# POVwatch_1.net
KiCad netlist of a schematic drawn in EAGLE
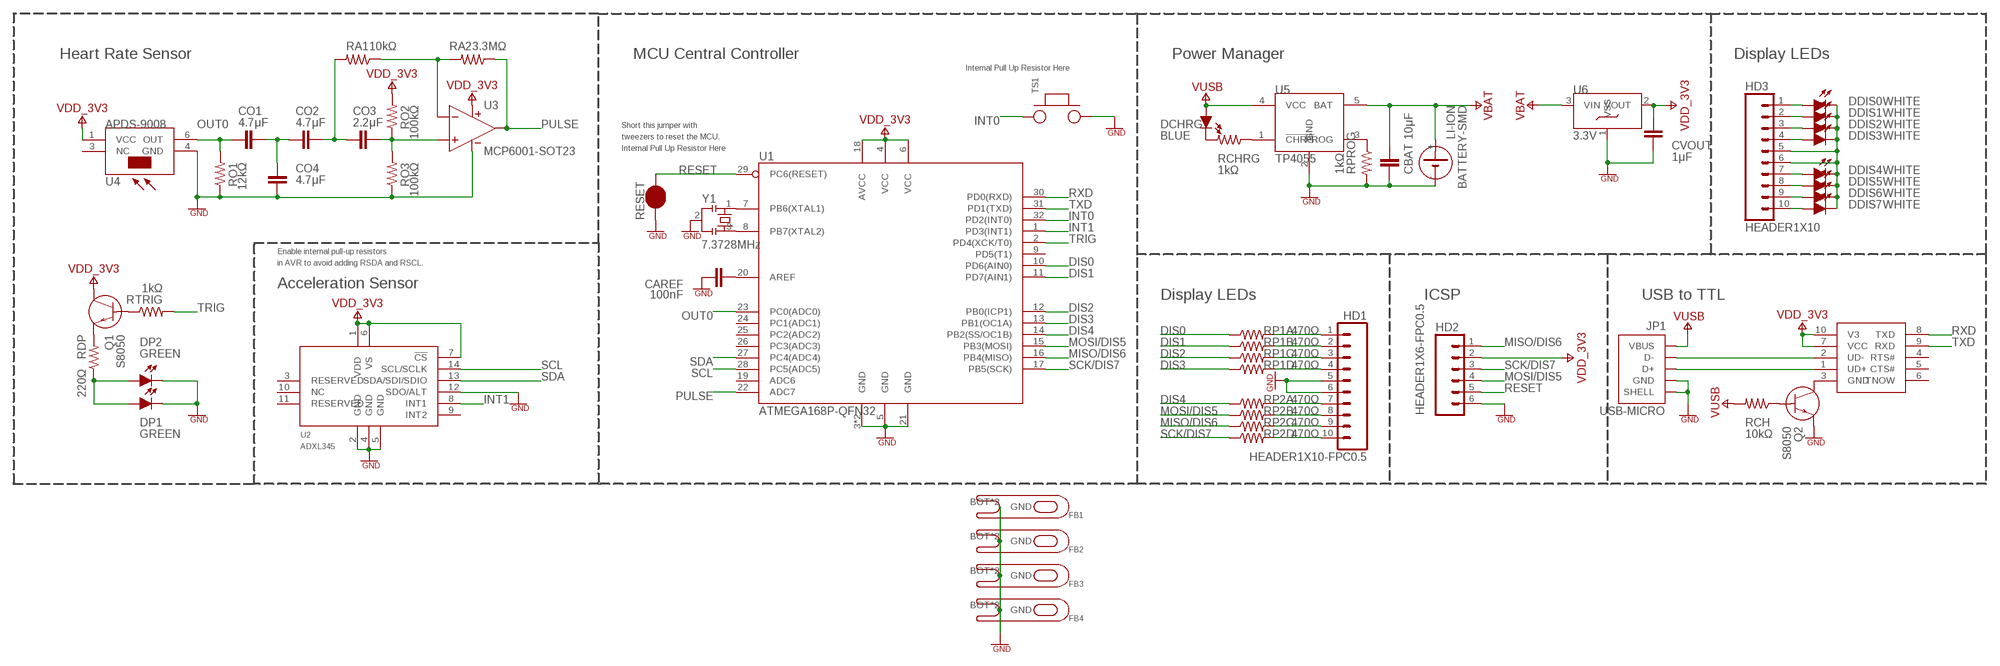
[diagram p0: schematic, sheet 1]

(export (version "E")
  (design (tool "Eeschema 10.0.6"))
  (components
    (comp (ref "CAREF")
      (value "100nF")
      (footprint "eagle-import:SMD0603")
      (libsource (lib "eagle-import") (part "CAP-0603"))
    )
    (comp (ref "CBAT")
      (value "10μF")
      (footprint "eagle-import:SMD0603")
      (libsource (lib "eagle-import") (part "CAP-0603"))
    )
    (comp (ref "CO1")
      (value "4.7μF")
      (footprint "eagle-import:SMD0603")
      (libsource (lib "eagle-import") (part "CAP-0603"))
    )
    (comp (ref "CO2")
      (value "4.7μF")
      (footprint "eagle-import:SMD0603")
      (libsource (lib "eagle-import") (part "CAP-0603"))
    )
    (comp (ref "CO3")
      (value "2.2μF")
      (footprint "eagle-import:SMD0603")
      (libsource (lib "eagle-import") (part "CAP-0603"))
    )
    (comp (ref "CO4")
      (value "4.7μF")
      (footprint "eagle-import:SMD0603")
      (libsource (lib "eagle-import") (part "CAP-0603"))
    )
    (comp (ref "CVOUT")
      (value "1μF")
      (footprint "eagle-import:SMD0603")
      (libsource (lib "eagle-import") (part "CAP-0603"))
    )
    (comp (ref "DCHRG")
      (value "BLUE")
      (footprint "eagle-import:LED-0603")
      (libsource (lib "eagle-import") (part "LED-0603"))
    )
    (comp (ref "DDIS0")
      (value "WHITE")
      (footprint "eagle-import:LED-0603")
      (libsource (lib "eagle-import") (part "LED-0603"))
    )
    (comp (ref "DDIS1")
      (value "WHITE")
      (footprint "eagle-import:LED-0603")
      (libsource (lib "eagle-import") (part "LED-0603"))
    )
    (comp (ref "DDIS2")
      (value "WHITE")
      (footprint "eagle-import:LED-0603")
      (libsource (lib "eagle-import") (part "LED-0603"))
    )
    (comp (ref "DDIS3")
      (value "WHITE")
      (footprint "eagle-import:LED-0603")
      (libsource (lib "eagle-import") (part "LED-0603"))
    )
    (comp (ref "DDIS4")
      (value "WHITE")
      (footprint "eagle-import:LED-0603")
      (libsource (lib "eagle-import") (part "LED-0603"))
    )
    (comp (ref "DDIS5")
      (value "WHITE")
      (footprint "eagle-import:LED-0603")
      (libsource (lib "eagle-import") (part "LED-0603"))
    )
    (comp (ref "DDIS6")
      (value "WHITE")
      (footprint "eagle-import:LED-0603")
      (libsource (lib "eagle-import") (part "LED-0603"))
    )
    (comp (ref "DDIS7")
      (value "WHITE")
      (footprint "eagle-import:LED-0603")
      (libsource (lib "eagle-import") (part "LED-0603"))
    )
    (comp (ref "DP1")
      (value "GREEN")
      (footprint "eagle-import:LED-1206")
      (libsource (lib "eagle-import") (part "LED-1206"))
    )
    (comp (ref "DP2")
      (value "GREEN")
      (footprint "eagle-import:LED-1206")
      (libsource (lib "eagle-import") (part "LED-1206"))
    )
    (comp (ref "FB1")
      (value "BROAD-STICK")
      (footprint "eagle-import:BOARD-STICK")
      (libsource (lib "eagle-import") (part "BROAD-STICK"))
    )
    (comp (ref "FB2")
      (value "BROAD-STICK")
      (footprint "eagle-import:BOARD-STICK")
      (libsource (lib "eagle-import") (part "BROAD-STICK"))
    )
    (comp (ref "FB3")
      (value "BROAD-STICK")
      (footprint "eagle-import:BOARD-STICK")
      (libsource (lib "eagle-import") (part "BROAD-STICK"))
    )
    (comp (ref "FB4")
      (value "BROAD-STICK")
      (footprint "eagle-import:BOARD-STICK")
      (libsource (lib "eagle-import") (part "BROAD-STICK"))
    )
    (comp (ref "HD1")
      (value "HEADER1X10-FPC0.5")
      (footprint "eagle-import:FPC0.5-10")
      (libsource (lib "eagle-import") (part "HEADER1X10-FPC0.5"))
    )
    (comp (ref "HD2")
      (value "HEADER1X6-FPC0.5")
      (footprint "eagle-import:FPC0.5-6")
      (libsource (lib "eagle-import") (part "HEADER1X6-FPC0.5"))
    )
    (comp (ref "HD3")
      (value "HEADER1X10")
      (footprint "eagle-import:FPC0.5-10-SOLDER")
      (libsource (lib "eagle-import") (part "HEADER1X10"))
    )
    (comp (ref "JP1")
      (value "USB-MICRO")
      (footprint "eagle-import:USB-MICRO")
      (libsource (lib "eagle-import") (part "USB-MICRO"))
    )
    (comp (ref "LI-ION")
      (value "BATTERY-SMD")
      (footprint "eagle-import:BAT-SMD")
      (libsource (lib "eagle-import") (part "BATTERY-SMD"))
    )
    (comp (ref "Q1")
      (value "S8050")
      (footprint "eagle-import:SOT23-0")
      (libsource (lib "eagle-import") (part "NPN-0"))
    )
    (comp (ref "Q2")
      (value "S8050")
      (footprint "eagle-import:SOT23-0")
      (libsource (lib "eagle-import") (part "NPN-0"))
    )
    (comp (ref "RA1")
      (value "10kΩ")
      (footprint "eagle-import:SMD0603")
      (libsource (lib "eagle-import") (part "RES-0603"))
    )
    (comp (ref "RA2")
      (value "3.3MΩ")
      (footprint "eagle-import:SMD0603")
      (libsource (lib "eagle-import") (part "RES-0603"))
    )
    (comp (ref "RCH")
      (value "10kΩ")
      (footprint "eagle-import:SMD0603")
      (libsource (lib "eagle-import") (part "RES-0603"))
    )
    (comp (ref "RCHRG")
      (value "1kΩ")
      (footprint "eagle-import:SMD0603")
      (libsource (lib "eagle-import") (part "RES-0603"))
    )
    (comp (ref "RDP")
      (value "220Ω")
      (footprint "eagle-import:SMD0603")
      (libsource (lib "eagle-import") (part "RES-0603"))
    )
    (comp (ref "RESET")
      (value "JUMPER-SMD")
      (footprint "eagle-import:JMPER-SMD")
      (libsource (lib "eagle-import") (part "JUMPER-SMD"))
    )
    (comp (ref "RO1")
      (value "12kΩ")
      (footprint "eagle-import:SMD0603")
      (libsource (lib "eagle-import") (part "RES-0603"))
    )
    (comp (ref "RO2")
      (value "100kΩ")
      (footprint "eagle-import:SMD0603")
      (libsource (lib "eagle-import") (part "RES-0603"))
    )
    (comp (ref "RO3")
      (value "100kΩ")
      (footprint "eagle-import:SMD0603")
      (libsource (lib "eagle-import") (part "RES-0603"))
    )
    (comp (ref "RP1")
      (value "470Ω")
      (footprint "eagle-import:RP0603")
      (libsource (lib "eagle-import") (part "RP-0603"))
    )
    (comp (ref "RP2")
      (value "470Ω")
      (footprint "eagle-import:RP0603")
      (libsource (lib "eagle-import") (part "RP-0603"))
    )
    (comp (ref "RPROG")
      (value "1kΩ")
      (footprint "eagle-import:SMD0603")
      (libsource (lib "eagle-import") (part "RES-0603"))
    )
    (comp (ref "RTRIG")
      (value "1kΩ")
      (footprint "eagle-import:SMD0603")
      (libsource (lib "eagle-import") (part "RES-0603"))
    )
    (comp (ref "TS1")
      (value "TS-P")
      (footprint "eagle-import:TS-3X4P")
      (libsource (lib "eagle-import") (part "TS-P"))
    )
    (comp (ref "U1")
      (value "ATMEGA168P-QFN32")
      (footprint "eagle-import:QFN32")
      (libsource (lib "eagle-import") (part "ATMEGA168P-QFN32"))
    )
    (comp (ref "U2")
      (value "ADXL345")
      (footprint "eagle-import:LGA14")
      (libsource (lib "eagle-import") (part "ADXL345"))
    )
    (comp (ref "U3")
      (value "MCP6001-SOT23")
      (footprint "eagle-import:SOT23-5")
      (libsource (lib "eagle-import") (part "MCP6001-SOT23"))
    )
    (comp (ref "U4")
      (value "APDS-9008")
      (footprint "eagle-import:APDS-9008")
      (libsource (lib "eagle-import") (part "APDS-9008"))
    )
    (comp (ref "U5")
      (value "TP4055")
      (footprint "eagle-import:SOT23-5")
      (libsource (lib "eagle-import") (part "TP4055"))
    )
    (comp (ref "U6")
      (value "3.3V")
      (footprint "eagle-import:SOT23-0")
      (libsource (lib "eagle-import") (part "XC6206-0"))
    )
    (comp (ref "U7")
      (value "CH340E")
      (footprint "eagle-import:MSOP10")
      (libsource (lib "eagle-import") (part "CH340E"))
    )
    (comp (ref "Y1")
      (value "7.3728MHz")
      (footprint "eagle-import:CSTCE")
      (libsource (lib "eagle-import") (part "CSTCE"))
    )
  )
  (nets
    (net (code "1") (name "/DIS0") (class "Default")
      (node (ref "RP1") (pin "1") (pinfunction "1_1") (pintype "passive"))
      (node (ref "U1") (pin "10") (pinfunction "PD6(AIN0)_10") (pintype "bidirectional"))
    )
    (net (code "2") (name "/DIS1") (class "Default")
      (node (ref "RP1") (pin "3") (pinfunction "1_3") (pintype "passive"))
      (node (ref "U1") (pin "11") (pinfunction "PD7(AIN1)_11") (pintype "bidirectional"))
    )
    (net (code "3") (name "/DIS2") (class "Default")
      (node (ref "RP1") (pin "5") (pinfunction "1_5") (pintype "passive"))
      (node (ref "U1") (pin "12") (pinfunction "PB0(ICP1)_12") (pintype "bidirectional"))
    )
    (net (code "4") (name "/DIS3") (class "Default")
      (node (ref "RP1") (pin "7") (pinfunction "1_7") (pintype "passive"))
      (node (ref "U1") (pin "13") (pinfunction "PB1(OC1A)_13") (pintype "bidirectional"))
    )
    (net (code "5") (name "/DIS4") (class "Default")
      (node (ref "RP2") (pin "1") (pinfunction "1_1") (pintype "passive"))
      (node (ref "U1") (pin "14") (pinfunction "PB2(SS/OC1B)_14") (pintype "bidirectional"))
    )
    (net (code "6") (name "/INT0") (class "Default")
      (node (ref "TS1") (pin "1") (pinfunction "1_1") (pintype "bidirectional"))
      (node (ref "U1") (pin "32") (pinfunction "PD2(INT0)_32") (pintype "bidirectional"))
    )
    (net (code "7") (name "/INT1") (class "Default")
      (node (ref "U1") (pin "1") (pinfunction "PD3(INT1)_1") (pintype "bidirectional"))
      (node (ref "U2") (pin "8") (pinfunction "INT1_8") (pintype "bidirectional"))
    )
    (net (code "8") (name "/MISO{slash}DIS6") (class "Default")
      (node (ref "HD2") (pin "1") (pinfunction "1_1") (pintype "passive"))
      (node (ref "RP2") (pin "5") (pinfunction "1_5") (pintype "passive"))
      (node (ref "U1") (pin "16") (pinfunction "PB4(MISO)_16") (pintype "bidirectional"))
    )
    (net (code "9") (name "/MOSI{slash}DIS5") (class "Default")
      (node (ref "HD2") (pin "4") (pinfunction "4_4") (pintype "passive"))
      (node (ref "RP2") (pin "3") (pinfunction "1_3") (pintype "passive"))
      (node (ref "U1") (pin "15") (pinfunction "PB3(MOSI)_15") (pintype "bidirectional"))
    )
    (net (code "10") (name "/OUT0") (class "Default")
      (node (ref "CO1") (pin "2") (pinfunction "2_2") (pintype "passive"))
      (node (ref "RO1") (pin "2") (pinfunction "2_2") (pintype "passive"))
      (node (ref "U1") (pin "23") (pinfunction "PC0(ADC0)_23") (pintype "bidirectional"))
      (node (ref "U4") (pin "6") (pinfunction "OUT_6") (pintype "bidirectional"))
    )
    (net (code "11") (name "/PULSE") (class "Default")
      (node (ref "RA2") (pin "1") (pinfunction "1_1") (pintype "passive"))
      (node (ref "U1") (pin "22") (pinfunction "ADC7_22") (pintype "bidirectional"))
      (node (ref "U3") (pin "1") (pinfunction "OUT_1") (pintype "passive"))
    )
    (net (code "12") (name "/RESET") (class "Default")
      (node (ref "HD2") (pin "5") (pinfunction "5_5") (pintype "passive"))
      (node (ref "RESET") (pin "2") (pinfunction "2_2") (pintype "passive"))
      (node (ref "U1") (pin "29") (pinfunction "PC6(RESET)_29") (pintype "bidirectional"))
    )
    (net (code "13") (name "/RXD") (class "Default")
      (node (ref "U1") (pin "30") (pinfunction "PD0(RXD)_30") (pintype "bidirectional"))
      (node (ref "U7") (pin "8") (pinfunction "TXD_8") (pintype "output"))
    )
    (net (code "14") (name "/SCK{slash}DIS7") (class "Default")
      (node (ref "HD2") (pin "3") (pinfunction "3_3") (pintype "passive"))
      (node (ref "RP2") (pin "7") (pinfunction "1_7") (pintype "passive"))
      (node (ref "U1") (pin "17") (pinfunction "PB5(SCK)_17") (pintype "bidirectional"))
    )
    (net (code "15") (name "/SCL") (class "Default")
      (node (ref "U1") (pin "28") (pinfunction "PC5(ADC5)_28") (pintype "bidirectional"))
      (node (ref "U2") (pin "14") (pinfunction "SCL/SCLK_14") (pintype "bidirectional"))
    )
    (net (code "16") (name "/SDA") (class "Default")
      (node (ref "U1") (pin "27") (pinfunction "PC4(ADC4)_27") (pintype "bidirectional"))
      (node (ref "U2") (pin "13") (pinfunction "SDA/SDI/SDIO_13") (pintype "bidirectional"))
    )
    (net (code "17") (name "/TRIG") (class "Default")
      (node (ref "RTRIG") (pin "2") (pinfunction "2_2") (pintype "passive"))
      (node (ref "U1") (pin "2") (pinfunction "PD4(XCK/T0)_2") (pintype "bidirectional"))
    )
    (net (code "18") (name "/TXD") (class "Default")
      (node (ref "U1") (pin "31") (pinfunction "PD1(TXD)_31") (pintype "bidirectional"))
      (node (ref "U7") (pin "9") (pinfunction "RXD_9") (pintype "input"))
    )
    (net (code "19") (name "GND") (class "Default")
      (node (ref "CAREF") (pin "1") (pinfunction "1_1") (pintype "passive"))
      (node (ref "CBAT") (pin "2") (pinfunction "2_2") (pintype "passive"))
      (node (ref "CO4") (pin "2") (pinfunction "2_2") (pintype "passive"))
      (node (ref "CVOUT") (pin "2") (pinfunction "2_2") (pintype "passive"))
      (node (ref "DP1") (pin "C") (pinfunction "C_C") (pintype "passive"))
      (node (ref "DP2") (pin "C") (pinfunction "C_C") (pintype "passive"))
      (node (ref "FB1") (pin "BOT") (pinfunction "GND_BOT") (pintype "bidirectional"))
      (node (ref "FB1") (pin "TOP") (pinfunction "GND_TOP") (pintype "bidirectional"))
      (node (ref "FB2") (pin "BOT") (pinfunction "GND_BOT") (pintype "bidirectional"))
      (node (ref "FB2") (pin "TOP") (pinfunction "GND_TOP") (pintype "bidirectional"))
      (node (ref "FB3") (pin "BOT") (pinfunction "GND_BOT") (pintype "bidirectional"))
      (node (ref "FB3") (pin "TOP") (pinfunction "GND_TOP") (pintype "bidirectional"))
      (node (ref "FB4") (pin "BOT") (pinfunction "GND_BOT") (pintype "bidirectional"))
      (node (ref "FB4") (pin "TOP") (pinfunction "GND_TOP") (pintype "bidirectional"))
      (node (ref "HD1") (pin "5") (pinfunction "5_5") (pintype "passive"))
      (node (ref "HD1") (pin "6") (pinfunction "6_6") (pintype "passive"))
      (node (ref "HD2") (pin "6") (pinfunction "6_6") (pintype "passive"))
      (node (ref "JP1") (pin "5") (pinfunction "GND_5") (pintype "bidirectional"))
      (node (ref "JP1") (pin "P1") (pinfunction "SHELL_P1") (pintype "bidirectional"))
      (node (ref "JP1") (pin "P2") (pinfunction "SHELL_P2") (pintype "bidirectional"))
      (node (ref "JP1") (pin "P3") (pinfunction "SHELL_P3") (pintype "bidirectional"))
      (node (ref "JP1") (pin "P4") (pinfunction "SHELL_P4") (pintype "bidirectional"))
      (node (ref "LI-ION") (pin "-") (pinfunction "-_-") (pintype "passive"))
      (node (ref "Q2") (pin "2") (pinfunction "E_2") (pintype "input"))
      (node (ref "RESET") (pin "1") (pinfunction "1_1") (pintype "passive"))
      (node (ref "RO1") (pin "1") (pinfunction "1_1") (pintype "passive"))
      (node (ref "RO3") (pin "1") (pinfunction "1_1") (pintype "passive"))
      (node (ref "RPROG") (pin "2") (pinfunction "2_2") (pintype "passive"))
      (node (ref "TS1") (pin "2") (pinfunction "2_2") (pintype "bidirectional"))
      (node (ref "U1") (pin "21") (pinfunction "GND_21") (pintype "bidirectional"))
      (node (ref "U1") (pin "3") (pinfunction "GND_3") (pintype "bidirectional"))
      (node (ref "U1") (pin "5") (pinfunction "GND_5") (pintype "bidirectional"))
      (node (ref "U1") (pin "EP") (pinfunction "GND_EP") (pintype "bidirectional"))
      (node (ref "U2") (pin "12") (pinfunction "SDO/ALT_12") (pintype "bidirectional"))
      (node (ref "U2") (pin "2") (pinfunction "GND_2") (pintype "bidirectional"))
      (node (ref "U2") (pin "4") (pinfunction "GND_4") (pintype "bidirectional"))
      (node (ref "U2") (pin "5") (pinfunction "GND_5") (pintype "bidirectional"))
      (node (ref "U3") (pin "2") (pinfunction "VSS_2") (pintype "passive"))
      (node (ref "U4") (pin "4") (pinfunction "GND_4") (pintype "bidirectional"))
      (node (ref "U5") (pin "2") (pinfunction "GND_2") (pintype "bidirectional"))
      (node (ref "U6") (pin "1") (pinfunction "VSS_1") (pintype "bidirectional"))
      (node (ref "Y1") (pin "2") (pinfunction "2_2") (pintype "passive"))
    )
    (net (code "20") (name "Net-(CO1-Pad1)") (class "Default")
      (node (ref "CO1") (pin "1") (pinfunction "1_1") (pintype "passive"))
      (node (ref "CO2") (pin "2") (pinfunction "2_2") (pintype "passive"))
      (node (ref "CO4") (pin "1") (pinfunction "1_1") (pintype "passive"))
    )
    (net (code "21") (name "Net-(CO2-Pad1)") (class "Default")
      (node (ref "CO2") (pin "1") (pinfunction "1_1") (pintype "passive"))
      (node (ref "CO3") (pin "2") (pinfunction "2_2") (pintype "passive"))
      (node (ref "RA1") (pin "2") (pinfunction "2_2") (pintype "passive"))
    )
    (net (code "22") (name "Net-(DCHRG-PadC)") (class "Default")
      (node (ref "DCHRG") (pin "C") (pinfunction "C_C") (pintype "passive"))
      (node (ref "RCHRG") (pin "2") (pinfunction "2_2") (pintype "passive"))
    )
    (net (code "23") (name "Net-(DDIS0-PadA)") (class "Default")
      (node (ref "DDIS0") (pin "A") (pinfunction "A_A") (pintype "passive"))
      (node (ref "HD3") (pin "1") (pinfunction "1_1") (pintype "passive"))
    )
    (net (code "24") (name "Net-(DDIS0-PadC)") (class "Default")
      (node (ref "DDIS0") (pin "C") (pinfunction "C_C") (pintype "passive"))
      (node (ref "DDIS1") (pin "C") (pinfunction "C_C") (pintype "passive"))
      (node (ref "DDIS2") (pin "C") (pinfunction "C_C") (pintype "passive"))
      (node (ref "DDIS3") (pin "C") (pinfunction "C_C") (pintype "passive"))
      (node (ref "DDIS4") (pin "C") (pinfunction "C_C") (pintype "passive"))
      (node (ref "DDIS5") (pin "C") (pinfunction "C_C") (pintype "passive"))
      (node (ref "DDIS6") (pin "C") (pinfunction "C_C") (pintype "passive"))
      (node (ref "DDIS7") (pin "C") (pinfunction "C_C") (pintype "passive"))
      (node (ref "HD3") (pin "5") (pinfunction "5_5") (pintype "passive"))
      (node (ref "HD3") (pin "6") (pinfunction "6_6") (pintype "passive"))
    )
    (net (code "25") (name "Net-(DDIS1-PadA)") (class "Default")
      (node (ref "DDIS1") (pin "A") (pinfunction "A_A") (pintype "passive"))
      (node (ref "HD3") (pin "2") (pinfunction "2_2") (pintype "passive"))
    )
    (net (code "26") (name "Net-(DDIS2-PadA)") (class "Default")
      (node (ref "DDIS2") (pin "A") (pinfunction "A_A") (pintype "passive"))
      (node (ref "HD3") (pin "3") (pinfunction "3_3") (pintype "passive"))
    )
    (net (code "27") (name "Net-(DDIS3-PadA)") (class "Default")
      (node (ref "DDIS3") (pin "A") (pinfunction "A_A") (pintype "passive"))
      (node (ref "HD3") (pin "4") (pinfunction "4_4") (pintype "passive"))
    )
    (net (code "28") (name "Net-(DDIS4-PadA)") (class "Default")
      (node (ref "DDIS4") (pin "A") (pinfunction "A_A") (pintype "passive"))
      (node (ref "HD3") (pin "7") (pinfunction "7_7") (pintype "passive"))
    )
    (net (code "29") (name "Net-(DDIS5-PadA)") (class "Default")
      (node (ref "DDIS5") (pin "A") (pinfunction "A_A") (pintype "passive"))
      (node (ref "HD3") (pin "8") (pinfunction "8_8") (pintype "passive"))
    )
    (net (code "30") (name "Net-(DDIS6-PadA)") (class "Default")
      (node (ref "DDIS6") (pin "A") (pinfunction "A_A") (pintype "passive"))
      (node (ref "HD3") (pin "9") (pinfunction "9_9") (pintype "passive"))
    )
    (net (code "31") (name "Net-(DDIS7-PadA)") (class "Default")
      (node (ref "DDIS7") (pin "A") (pinfunction "A_A") (pintype "passive"))
      (node (ref "HD3") (pin "10") (pinfunction "10_10") (pintype "passive"))
    )
    (net (code "32") (name "Net-(DP1-PadA)") (class "Default")
      (node (ref "DP1") (pin "A") (pinfunction "A_A") (pintype "passive"))
      (node (ref "DP2") (pin "A") (pinfunction "A_A") (pintype "passive"))
      (node (ref "RDP") (pin "1") (pinfunction "1_1") (pintype "passive"))
    )
    (net (code "33") (name "Net-(HD1-Pad1)") (class "Default")
      (node (ref "HD1") (pin "1") (pinfunction "1_1") (pintype "passive"))
      (node (ref "RP1") (pin "2") (pinfunction "2_2") (pintype "passive"))
    )
    (net (code "34") (name "Net-(HD1-Pad7)") (class "Default")
      (node (ref "HD1") (pin "7") (pinfunction "7_7") (pintype "passive"))
      (node (ref "RP2") (pin "2") (pinfunction "2_2") (pintype "passive"))
    )
    (net (code "35") (name "Net-(JP1-D+)") (class "Default")
      (node (ref "JP1") (pin "3") (pinfunction "D+_3") (pintype "bidirectional"))
      (node (ref "U7") (pin "1") (pinfunction "UD+_1") (pintype "bidirectional"))
    )
    (net (code "36") (name "Net-(JP1-D-)") (class "Default")
      (node (ref "JP1") (pin "2") (pinfunction "D-_2") (pintype "bidirectional"))
      (node (ref "U7") (pin "2") (pinfunction "UD-_2") (pintype "bidirectional"))
    )
    (net (code "37") (name "Net-(Q1-B)") (class "Default")
      (node (ref "Q1") (pin "1") (pinfunction "B_1") (pintype "input"))
      (node (ref "RTRIG") (pin "1") (pinfunction "1_1") (pintype "passive"))
    )
    (net (code "38") (name "Net-(Q1-E)") (class "Default")
      (node (ref "Q1") (pin "2") (pinfunction "E_2") (pintype "input"))
      (node (ref "RDP") (pin "2") (pinfunction "2_2") (pintype "passive"))
    )
    (net (code "39") (name "Net-(Q2-B)") (class "Default")
      (node (ref "Q2") (pin "1") (pinfunction "B_1") (pintype "input"))
      (node (ref "RCH") (pin "1") (pinfunction "1_1") (pintype "passive"))
    )
    (net (code "40") (name "Net-(Q2-C)") (class "Default")
      (node (ref "Q2") (pin "3") (pinfunction "C_3") (pintype "input"))
      (node (ref "U7") (pin "3") (pinfunction "GND_3") (pintype "bidirectional"))
    )
    (net (code "41") (name "Net-(RP1B-2)") (class "Default")
      (node (ref "HD1") (pin "2") (pinfunction "2_2") (pintype "passive"))
      (node (ref "RP1") (pin "4") (pinfunction "2_4") (pintype "passive"))
    )
    (net (code "42") (name "Net-(RP1C-2)") (class "Default")
      (node (ref "HD1") (pin "3") (pinfunction "3_3") (pintype "passive"))
      (node (ref "RP1") (pin "6") (pinfunction "2_6") (pintype "passive"))
    )
    (net (code "43") (name "Net-(RP1D-2)") (class "Default")
      (node (ref "HD1") (pin "4") (pinfunction "4_4") (pintype "passive"))
      (node (ref "RP1") (pin "8") (pinfunction "2_8") (pintype "passive"))
    )
    (net (code "44") (name "Net-(RP2B-2)") (class "Default")
      (node (ref "HD1") (pin "8") (pinfunction "8_8") (pintype "passive"))
      (node (ref "RP2") (pin "4") (pinfunction "2_4") (pintype "passive"))
    )
    (net (code "45") (name "Net-(RP2C-2)") (class "Default")
      (node (ref "HD1") (pin "9") (pinfunction "9_9") (pintype "passive"))
      (node (ref "RP2") (pin "6") (pinfunction "2_6") (pintype "passive"))
    )
    (net (code "46") (name "Net-(RP2D-2)") (class "Default")
      (node (ref "HD1") (pin "10") (pinfunction "10_10") (pintype "passive"))
      (node (ref "RP2") (pin "8") (pinfunction "2_8") (pintype "passive"))
    )
    (net (code "47") (name "Net-(U1-AREF)") (class "Default")
      (node (ref "CAREF") (pin "2") (pinfunction "2_2") (pintype "passive"))
      (node (ref "U1") (pin "20") (pinfunction "AREF_20") (pintype "bidirectional"))
    )
    (net (code "48") (name "Net-(U1-PB6(XTAL1))") (class "Default")
      (node (ref "U1") (pin "7") (pinfunction "PB6(XTAL1)_7") (pintype "bidirectional"))
      (node (ref "Y1") (pin "1") (pinfunction "1_1") (pintype "passive"))
    )
    (net (code "49") (name "Net-(U1-PB7(XTAL2))") (class "Default")
      (node (ref "U1") (pin "8") (pinfunction "PB7(XTAL2)_8") (pintype "bidirectional"))
      (node (ref "Y1") (pin "3") (pinfunction "3_3") (pintype "passive"))
    )
    (net (code "50") (name "Net-(U3-IN+)") (class "Default")
      (node (ref "CO3") (pin "1") (pinfunction "1_1") (pintype "passive"))
      (node (ref "RO2") (pin "1") (pinfunction "1_1") (pintype "passive"))
      (node (ref "RO3") (pin "2") (pinfunction "2_2") (pintype "passive"))
      (node (ref "U3") (pin "3") (pinfunction "IN+_3") (pintype "passive"))
    )
    (net (code "51") (name "Net-(U3-IN-)") (class "Default")
      (node (ref "RA1") (pin "1") (pinfunction "1_1") (pintype "passive"))
      (node (ref "RA2") (pin "2") (pinfunction "2_2") (pintype "passive"))
      (node (ref "U3") (pin "4") (pinfunction "IN-_4") (pintype "passive"))
    )
    (net (code "52") (name "Net-(U5-PROG)") (class "Default")
      (node (ref "RPROG") (pin "1") (pinfunction "1_1") (pintype "passive"))
      (node (ref "U5") (pin "3") (pinfunction "PROG_3") (pintype "bidirectional"))
    )
    (net (code "53") (name "Net-(U5-~{CHRG})") (class "Default")
      (node (ref "RCHRG") (pin "1") (pinfunction "1_1") (pintype "passive"))
      (node (ref "U5") (pin "1") (pinfunction "~{CHRG}_1") (pintype "bidirectional"))
    )
    (net (code "54") (name "VBAT") (class "Default")
      (node (ref "CBAT") (pin "1") (pinfunction "1_1") (pintype "passive"))
      (node (ref "LI-ION") (pin "+") (pinfunction "+_+") (pintype "passive"))
      (node (ref "U5") (pin "5") (pinfunction "BAT_5") (pintype "bidirectional"))
      (node (ref "U6") (pin "3") (pinfunction "VIN_3") (pintype "bidirectional"))
    )
    (net (code "55") (name "VDD_3V3") (class "Default")
      (node (ref "CVOUT") (pin "1") (pinfunction "1_1") (pintype "passive"))
      (node (ref "HD2") (pin "2") (pinfunction "2_2") (pintype "passive"))
      (node (ref "Q1") (pin "3") (pinfunction "C_3") (pintype "input"))
      (node (ref "RO2") (pin "2") (pinfunction "2_2") (pintype "passive"))
      (node (ref "U1") (pin "18") (pinfunction "AVCC_18") (pintype "bidirectional"))
      (node (ref "U1") (pin "4") (pinfunction "VCC_4") (pintype "bidirectional"))
      (node (ref "U1") (pin "6") (pinfunction "VCC_6") (pintype "bidirectional"))
      (node (ref "U2") (pin "1") (pinfunction "VDD_1") (pintype "bidirectional"))
      (node (ref "U2") (pin "6") (pinfunction "VS_6") (pintype "bidirectional"))
      (node (ref "U2") (pin "7") (pinfunction "~{CS}_7") (pintype "bidirectional"))
      (node (ref "U3") (pin "5") (pinfunction "VDD_5") (pintype "passive"))
      (node (ref "U4") (pin "1") (pinfunction "VCC_1") (pintype "bidirectional"))
      (node (ref "U6") (pin "2") (pinfunction "VOUT_2") (pintype "bidirectional"))
      (node (ref "U7") (pin "10") (pinfunction "V3_10") (pintype "bidirectional"))
      (node (ref "U7") (pin "7") (pinfunction "VCC_7") (pintype "bidirectional"))
    )
    (net (code "56") (name "VUSB") (class "Default")
      (node (ref "DCHRG") (pin "A") (pinfunction "A_A") (pintype "passive"))
      (node (ref "JP1") (pin "1") (pinfunction "VBUS_1") (pintype "bidirectional"))
      (node (ref "RCH") (pin "2") (pinfunction "2_2") (pintype "passive"))
      (node (ref "U5") (pin "4") (pinfunction "VCC_4") (pintype "bidirectional"))
    )
    (net (code "57") (name "unconnected-(U1-ADC6-Pad19)") (class "Default")
      (node (ref "U1") (pin "19") (pinfunction "ADC6_19") (pintype "bidirectional"))
    )
    (net (code "58") (name "unconnected-(U1-PC1(ADC1)-Pad24)") (class "Default")
      (node (ref "U1") (pin "24") (pinfunction "PC1(ADC1)_24") (pintype "bidirectional"))
    )
    (net (code "59") (name "unconnected-(U1-PC2(ADC2)-Pad25)") (class "Default")
      (node (ref "U1") (pin "25") (pinfunction "PC2(ADC2)_25") (pintype "bidirectional"))
    )
    (net (code "60") (name "unconnected-(U1-PC3(ADC3)-Pad26)") (class "Default")
      (node (ref "U1") (pin "26") (pinfunction "PC3(ADC3)_26") (pintype "bidirectional"))
    )
    (net (code "61") (name "unconnected-(U1-PD5(T1)-Pad9)") (class "Default")
      (node (ref "U1") (pin "9") (pinfunction "PD5(T1)_9") (pintype "bidirectional"))
    )
    (net (code "62") (name "unconnected-(U2-INT2-Pad9)") (class "Default")
      (node (ref "U2") (pin "9") (pinfunction "INT2_9") (pintype "bidirectional"))
    )
    (net (code "63") (name "unconnected-(U2-NC-Pad10)") (class "Default")
      (node (ref "U2") (pin "10") (pinfunction "NC_10") (pintype "bidirectional"))
    )
    (net (code "64") (name "unconnected-(U2-RESERVED-Pad3)") (class "Default")
      (node (ref "U2") (pin "3") (pinfunction "RESERVED_3") (pintype "bidirectional"))
    )
    (net (code "65") (name "unconnected-(U2-RESERVED-Pad11)") (class "Default")
      (node (ref "U2") (pin "11") (pinfunction "RESERVED_11") (pintype "bidirectional"))
    )
    (net (code "66") (name "unconnected-(U4-NC-Pad3)") (class "Default")
      (node (ref "U4") (pin "3") (pinfunction "NC_3") (pintype "bidirectional"))
    )
    (net (code "67") (name "unconnected-(U7-CTS#-Pad5)") (class "Default")
      (node (ref "U7") (pin "5") (pinfunction "CTS#_5") (pintype "bidirectional"))
    )
    (net (code "68") (name "unconnected-(U7-RTS#-Pad4)") (class "Default")
      (node (ref "U7") (pin "4") (pinfunction "RTS#_4") (pintype "bidirectional"))
    )
    (net (code "69") (name "unconnected-(U7-TNOW-Pad6)") (class "Default")
      (node (ref "U7") (pin "6") (pinfunction "TNOW_6") (pintype "bidirectional"))
    )
  )
)
